# CFcard.net
KiCad netlist of a schematic drawn in Altium Designer
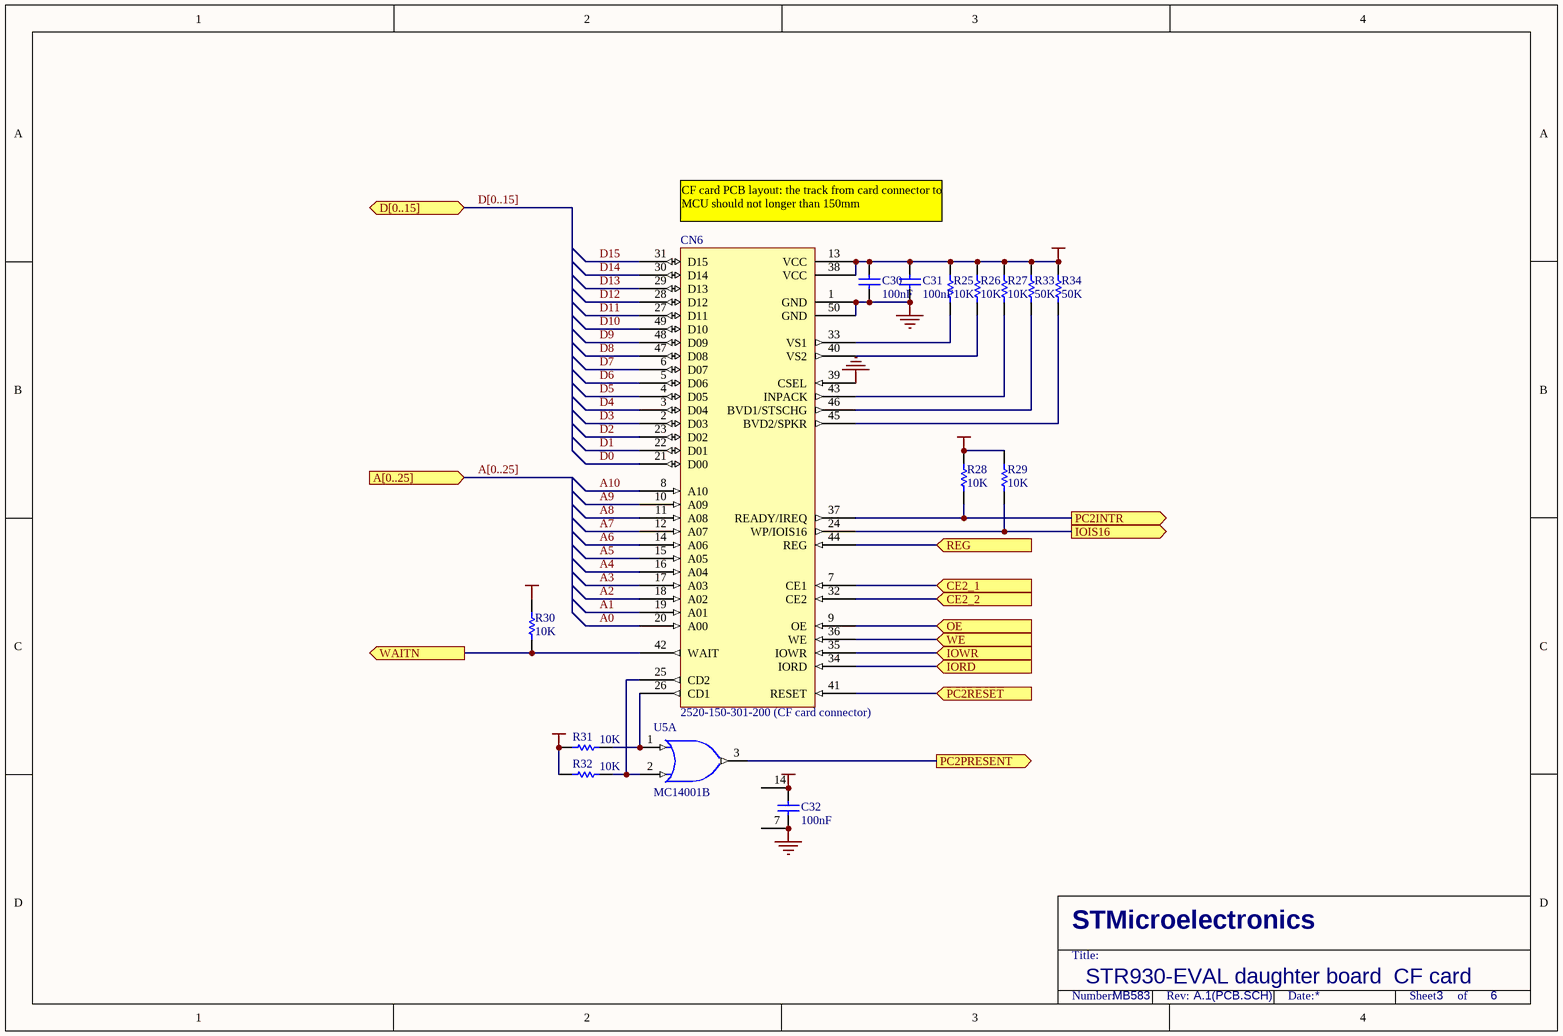
[diagram p0: CFcard.SchDoc]

(export (version "E")
  (design (tool "Eeschema 10.0.6"))
  (components
    (comp (ref "C30")
      (value "100nF")
      (footprint "0603")
      (description "Capacitor")
      (fields (field (name "PUBLISHER") "Altium Limited"))
      (libsource (lib "Miscellaneous Devices") (part "cap"))
    )
    (comp (ref "C31")
      (value "100nF")
      (footprint "0603")
      (description "Capacitor")
      (fields (field (name "PUBLISHER") "Altium Limited"))
      (libsource (lib "Miscellaneous Devices") (part "cap"))
    )
    (comp (ref "C32")
      (value "100nF")
      (footprint "0603")
      (description "Capacitor")
      (fields (field (name "PUBLISHER") "Altium Limited"))
      (libsource (lib "Miscellaneous Devices") (part "cap"))
    )
    (comp (ref "CN6")
      (value "2520-150-301-200 (CF card connector)")
      (description "CF card connector")
      (libsource (lib "STR93x-EVAL") (part "2520-150-301-200"))
    )
    (comp (ref "R25")
      (value "10K")
      (description "Resistor")
      (fields (field (name "PUBLISHER") "Altium Limited"))
      (libsource (lib "Miscellaneous Devices") (part "Res1"))
    )
    (comp (ref "R26")
      (value "10K")
      (description "Resistor")
      (fields (field (name "PUBLISHER") "Altium Limited"))
      (libsource (lib "Miscellaneous Devices") (part "Res1"))
    )
    (comp (ref "R27")
      (value "10K")
      (description "Resistor")
      (fields (field (name "PUBLISHER") "Altium Limited"))
      (libsource (lib "Miscellaneous Devices") (part "Res1"))
    )
    (comp (ref "R28")
      (value "10K")
      (description "Resistor")
      (fields (field (name "PUBLISHER") "Altium Limited"))
      (libsource (lib "Miscellaneous Devices") (part "Res1"))
    )
    (comp (ref "R29")
      (value "10K")
      (description "Resistor")
      (fields (field (name "PUBLISHER") "Altium Limited"))
      (libsource (lib "Miscellaneous Devices") (part "Res1"))
    )
    (comp (ref "R30")
      (value "10K")
      (description "Resistor")
      (fields (field (name "PUBLISHER") "Altium Limited"))
      (libsource (lib "Miscellaneous Devices") (part "Res1"))
    )
    (comp (ref "R31")
      (value "10K")
      (description "Resistor")
      (fields (field (name "PUBLISHER") "Altium Limited"))
      (libsource (lib "Miscellaneous Devices") (part "Res1"))
    )
    (comp (ref "R32")
      (value "10K")
      (description "Resistor")
      (fields (field (name "PUBLISHER") "Altium Limited"))
      (libsource (lib "Miscellaneous Devices") (part "Res1"))
    )
    (comp (ref "R33")
      (value "50K")
      (description "Resistor")
      (fields (field (name "PUBLISHER") "Altium Limited"))
      (libsource (lib "Miscellaneous Devices") (part "Res1"))
    )
    (comp (ref "R34")
      (value "50K")
      (description "Resistor")
      (fields (field (name "PUBLISHER") "Altium Limited"))
      (libsource (lib "Miscellaneous Devices") (part "Res1"))
    )
    (comp (ref "U5")
      (value "MC14001B")
      (description "Quad 2-Input OR Gate")
      (fields (field (name "PUBLISHER") "Altium Limited"))
      (libsource (lib "ST Logic Gate") (part "74AC32B"))
    )
  )
  (nets
    (net (code "16") (name "+3V3") (class "Default")
      (node (ref "C30") (pin "2") (pinfunction "2_2") (pintype "passive"))
      (node (ref "C31") (pin "2") (pinfunction "2_2") (pintype "passive"))
      (node (ref "C32") (pin "1") (pinfunction "1_1") (pintype "passive"))
      (node (ref "CN6") (pin "13") (pinfunction "VCC_13") (pintype "passive"))
      (node (ref "CN6") (pin "38") (pinfunction "VCC_38") (pintype "passive"))
      (node (ref "R25") (pin "1") (pinfunction "1_1") (pintype "passive"))
      (node (ref "R26") (pin "1") (pinfunction "1_1") (pintype "passive"))
      (node (ref "R27") (pin "1") (pinfunction "1_1") (pintype "passive"))
      (node (ref "R28") (pin "2") (pinfunction "2_2") (pintype "passive"))
      (node (ref "R29") (pin "2") (pinfunction "2_2") (pintype "passive"))
      (node (ref "R30") (pin "2") (pinfunction "2_2") (pintype "passive"))
      (node (ref "R31") (pin "1") (pinfunction "1_1") (pintype "passive"))
      (node (ref "R32") (pin "1") (pinfunction "1_1") (pintype "passive"))
      (node (ref "R33") (pin "1") (pinfunction "1_1") (pintype "passive"))
      (node (ref "R34") (pin "1") (pinfunction "1_1") (pintype "passive"))
      (node (ref "U5") (pin "14") (pinfunction "VCC_14") (pintype "power_in"))
    )
    (net (code "17") (name "/A0") (class "Default")
      (node (ref "CN6") (pin "20") (pinfunction "A00_20") (pintype "input"))
    )
    (net (code "18") (name "/A1") (class "Default")
      (node (ref "CN6") (pin "19") (pinfunction "A01_19") (pintype "input"))
    )
    (net (code "19") (name "/A2") (class "Default")
      (node (ref "CN6") (pin "18") (pinfunction "A02_18") (pintype "input"))
    )
    (net (code "20") (name "/A3") (class "Default")
      (node (ref "CN6") (pin "17") (pinfunction "A03_17") (pintype "input"))
    )
    (net (code "21") (name "/A4") (class "Default")
      (node (ref "CN6") (pin "16") (pinfunction "A04_16") (pintype "input"))
    )
    (net (code "22") (name "/A5") (class "Default")
      (node (ref "CN6") (pin "15") (pinfunction "A05_15") (pintype "input"))
    )
    (net (code "23") (name "/A6") (class "Default")
      (node (ref "CN6") (pin "14") (pinfunction "A06_14") (pintype "input"))
    )
    (net (code "24") (name "/A7") (class "Default")
      (node (ref "CN6") (pin "12") (pinfunction "A07_12") (pintype "input"))
    )
    (net (code "25") (name "/A8") (class "Default")
      (node (ref "CN6") (pin "11") (pinfunction "A08_11") (pintype "input"))
    )
    (net (code "26") (name "/A9") (class "Default")
      (node (ref "CN6") (pin "10") (pinfunction "A09_10") (pintype "input"))
    )
    (net (code "27") (name "/A10") (class "Default")
      (node (ref "CN6") (pin "8") (pinfunction "A10_8") (pintype "input"))
    )
    (net (code "29") (name "/CE2_1") (class "Default")
      (node (ref "CN6") (pin "7") (pinfunction "CE1_7") (pintype "input"))
    )
    (net (code "30") (name "/CE2_2") (class "Default")
      (node (ref "CN6") (pin "32") (pinfunction "CE2_32") (pintype "input"))
    )
    (net (code "31") (name "/D0") (class "Default")
      (node (ref "CN6") (pin "21") (pinfunction "D00_21") (pintype "bidirectional"))
    )
    (net (code "32") (name "/D1") (class "Default")
      (node (ref "CN6") (pin "22") (pinfunction "D01_22") (pintype "bidirectional"))
    )
    (net (code "33") (name "/D2") (class "Default")
      (node (ref "CN6") (pin "23") (pinfunction "D02_23") (pintype "bidirectional"))
    )
    (net (code "34") (name "/D3") (class "Default")
      (node (ref "CN6") (pin "2") (pinfunction "D03_2") (pintype "bidirectional"))
    )
    (net (code "35") (name "/D4") (class "Default")
      (node (ref "CN6") (pin "3") (pinfunction "D04_3") (pintype "bidirectional"))
    )
    (net (code "36") (name "/D5") (class "Default")
      (node (ref "CN6") (pin "4") (pinfunction "D05_4") (pintype "bidirectional"))
    )
    (net (code "37") (name "/D6") (class "Default")
      (node (ref "CN6") (pin "5") (pinfunction "D06_5") (pintype "bidirectional"))
    )
    (net (code "38") (name "/D7") (class "Default")
      (node (ref "CN6") (pin "6") (pinfunction "D07_6") (pintype "bidirectional"))
    )
    (net (code "39") (name "/D8") (class "Default")
      (node (ref "CN6") (pin "47") (pinfunction "D08_47") (pintype "bidirectional"))
    )
    (net (code "40") (name "/D9") (class "Default")
      (node (ref "CN6") (pin "48") (pinfunction "D09_48") (pintype "bidirectional"))
    )
    (net (code "41") (name "/D10") (class "Default")
      (node (ref "CN6") (pin "49") (pinfunction "D10_49") (pintype "bidirectional"))
    )
    (net (code "42") (name "/D11") (class "Default")
      (node (ref "CN6") (pin "27") (pinfunction "D11_27") (pintype "bidirectional"))
    )
    (net (code "43") (name "/D12") (class "Default")
      (node (ref "CN6") (pin "28") (pinfunction "D12_28") (pintype "bidirectional"))
    )
    (net (code "44") (name "/D13") (class "Default")
      (node (ref "CN6") (pin "29") (pinfunction "D13_29") (pintype "bidirectional"))
    )
    (net (code "45") (name "/D14") (class "Default")
      (node (ref "CN6") (pin "30") (pinfunction "D14_30") (pintype "bidirectional"))
    )
    (net (code "46") (name "/D15") (class "Default")
      (node (ref "CN6") (pin "31") (pinfunction "D15_31") (pintype "bidirectional"))
    )
    (net (code "48") (name "/IOIS16") (class "Default")
      (node (ref "CN6") (pin "24") (pinfunction "WP/IOIS16_24") (pintype "output"))
      (node (ref "R29") (pin "1") (pinfunction "1_1") (pintype "passive"))
    )
    (net (code "49") (name "/IORD") (class "Default")
      (node (ref "CN6") (pin "34") (pinfunction "IORD_34") (pintype "input"))
    )
    (net (code "50") (name "/IOWR") (class "Default")
      (node (ref "CN6") (pin "35") (pinfunction "IOWR_35") (pintype "input"))
    )
    (net (code "51") (name "/OE") (class "Default")
      (node (ref "CN6") (pin "9") (pinfunction "OE_9") (pintype "input"))
    )
    (net (code "52") (name "/PC2INTR") (class "Default")
      (node (ref "CN6") (pin "37") (pinfunction "READY/IREQ_37") (pintype "output"))
      (node (ref "R28") (pin "1") (pinfunction "1_1") (pintype "passive"))
    )
    (net (code "53") (name "/PC2PRESENT") (class "Default")
      (node (ref "U5") (pin "3") (pinfunction "Y_3") (pintype "output"))
    )
    (net (code "54") (name "/PC2RESET") (class "Default")
      (node (ref "CN6") (pin "41") (pinfunction "RESET_41") (pintype "input"))
    )
    (net (code "55") (name "/REG") (class "Default")
      (node (ref "CN6") (pin "44") (pinfunction "REG_44") (pintype "input"))
    )
    (net (code "56") (name "/WAITN") (class "Default")
      (node (ref "CN6") (pin "42") (pinfunction "WAIT_42") (pintype "output"))
      (node (ref "R30") (pin "1") (pinfunction "1_1") (pintype "passive"))
    )
    (net (code "57") (name "/WE") (class "Default")
      (node (ref "CN6") (pin "36") (pinfunction "WE_36") (pintype "input"))
    )
    (net (code "58") (name "GND") (class "Default")
      (node (ref "C30") (pin "1") (pinfunction "1_1") (pintype "passive"))
      (node (ref "C31") (pin "1") (pinfunction "1_1") (pintype "passive"))
      (node (ref "C32") (pin "2") (pinfunction "2_2") (pintype "passive"))
      (node (ref "CN6") (pin "1") (pinfunction "GND_1") (pintype "passive"))
      (node (ref "CN6") (pin "39") (pinfunction "CSEL_39") (pintype "input"))
      (node (ref "CN6") (pin "50") (pinfunction "GND_50") (pintype "passive"))
      (node (ref "U5") (pin "7") (pinfunction "GND_7") (pintype "power_in"))
    )
    (net (code "59") (name "Net-(CN6-BVD1{slash}STSCHG)") (class "Default")
      (node (ref "CN6") (pin "46") (pinfunction "BVD1/STSCHG_46") (pintype "output"))
      (node (ref "R33") (pin "2") (pinfunction "2_2") (pintype "passive"))
    )
    (net (code "60") (name "Net-(CN6-BVD2{slash}SPKR)") (class "Default")
      (node (ref "CN6") (pin "45") (pinfunction "BVD2/SPKR_45") (pintype "output"))
      (node (ref "R34") (pin "2") (pinfunction "2_2") (pintype "passive"))
    )
    (net (code "61") (name "Net-(CN6-CD1)") (class "Default")
      (node (ref "CN6") (pin "26") (pinfunction "CD1_26") (pintype "output"))
      (node (ref "R31") (pin "2") (pinfunction "2_2") (pintype "passive"))
      (node (ref "U5") (pin "1") (pinfunction "A_1") (pintype "input"))
    )
    (net (code "62") (name "Net-(CN6-CD2)") (class "Default")
      (node (ref "CN6") (pin "25") (pinfunction "CD2_25") (pintype "output"))
      (node (ref "R32") (pin "2") (pinfunction "2_2") (pintype "passive"))
      (node (ref "U5") (pin "2") (pinfunction "B_2") (pintype "input"))
    )
    (net (code "63") (name "Net-(CN6-INPACK)") (class "Default")
      (node (ref "CN6") (pin "43") (pinfunction "INPACK_43") (pintype "output"))
      (node (ref "R27") (pin "2") (pinfunction "2_2") (pintype "passive"))
    )
    (net (code "64") (name "Net-(CN6-VS1)") (class "Default")
      (node (ref "CN6") (pin "33") (pinfunction "VS1_33") (pintype "output"))
      (node (ref "R25") (pin "2") (pinfunction "2_2") (pintype "passive"))
    )
    (net (code "65") (name "Net-(CN6-VS2)") (class "Default")
      (node (ref "CN6") (pin "40") (pinfunction "VS2_40") (pintype "output"))
      (node (ref "R26") (pin "2") (pinfunction "2_2") (pintype "passive"))
    )
  )
)
